# PFC_15V_PwrSRegulator.net
KiCad netlist of a schematic drawn in Altium Designer
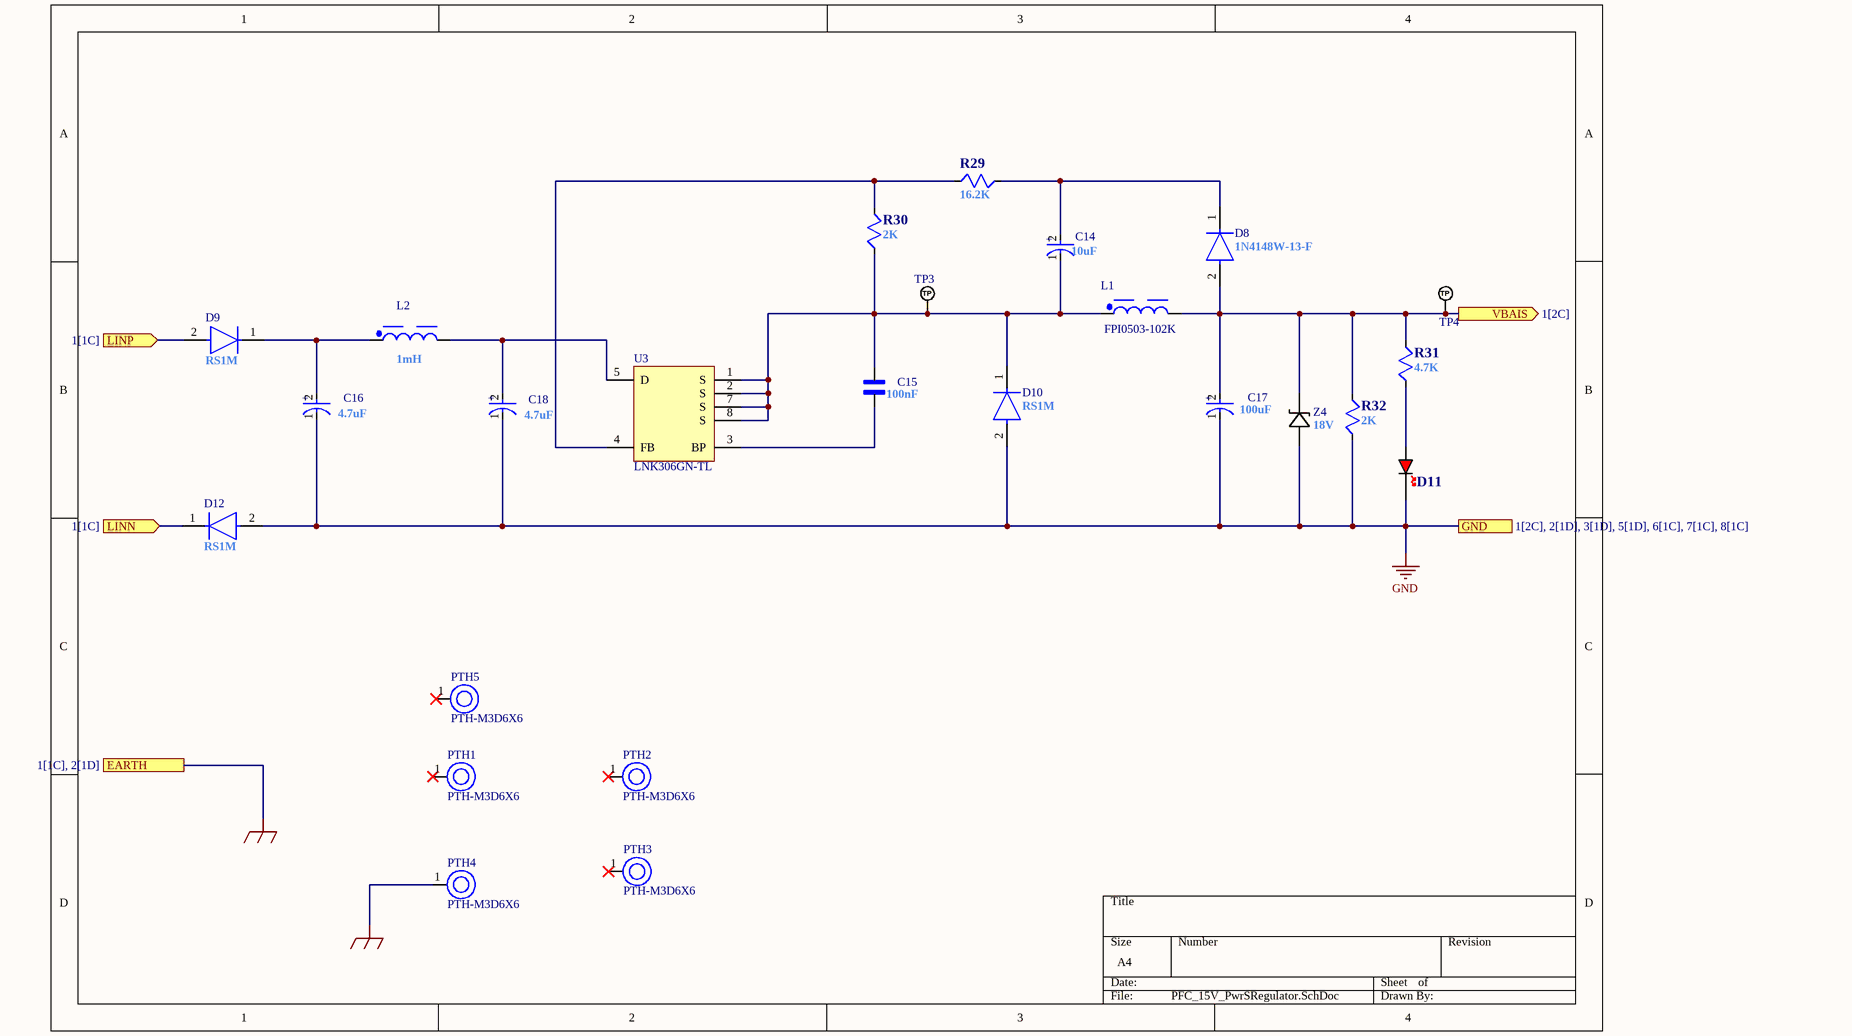
[diagram p0: PFC_15V_PwrSRegulator.SchDoc]

(export (version "E")
  (design (tool "Eeschema 10.0.6"))
  (components
    (comp (ref "C14")
      (value "SC1V106M05005VR")
      (footprint "FP-FKC-MFG")
      (description "CAP.EL.10uF 35V 5x5.3 85C SMD SAMWHA")
      (fields
        (field (name "TOLERANCE") "20%")
        (field (name "VOLTAGE") "35V")
        (field (name "CAPACITANCE") "10uF")
      )
      (libsource (lib "Altium Content Vault") (part "a00bbbee19879c290e62620ae7e47b1"))
    )
    (comp (ref "C15")
      (value "100nF")
      (footprint "CAPC3216X140N")
      (description "0.1 ÂµF Â±10% 250V Ceramic Capacitor X7R 1206 (3216 Metric)")
      (fields (field (name "MF") "KEMET") (field (name "MP") "C1206C104KARECAUTO"))
      (libsource (lib "Görev Yükü's Libary") (part "C1206C104KARECAUTO"))
    )
    (comp (ref "C16")
      (value "PKLH-400V4R7MG125-T/A5.0")
      (footprint "FP-RAD-TH-D_10_0_5-L_12_5-MFG")
      (description "CAP.EL.4u7 400V 10X12.5 5MM %20 105C LOW IMP")
      (fields (field (name "TOLERANCE") "20%") (field (name "CAPACITANCE") "4.7uF"))
      (libsource (lib "Altium Content Vault") (part "203bc49f2ac43e59fd269a8c329ed05"))
    )
    (comp (ref "C17")
      (value "CKL025M101F10PKKKV00A")
      (footprint "FP-SEV8X10_5-MFG")
      (description "CAP.EL.100uF 25V 8x10 105C 5000H AEC-Q200 SMT")
      (fields (field (name "CAPACITANCE") "100uF") (field (name "TOLERANCE") "20%"))
      (libsource (lib "Altium Content Vault") (part "203bc49f2ac43e59fd269a8c329ed05"))
    )
    (comp (ref "C18")
      (value "PKLH-400V4R7MG125-T/A5.0")
      (footprint "FP-RAD-TH-D_10_0_5-L_12_5-MFG")
      (description "CAP.EL.4u7 400V 10X12.5 5MM %20 105C LOW IMP")
      (fields (field (name "TOLERANCE") "20%") (field (name "CAPACITANCE") "4.7uF"))
      (libsource (lib "Altium Content Vault") (part "203bc49f2ac43e59fd269a8c329ed05"))
    )
    (comp (ref "D8")
      (value "1N4148W-13-F")
      (footprint "FP-SOD123-MFG")
      (description "DIODE GEN PURP 100V 150MA SOD123")
      (fields
        (field (name "OCTOPART") "https://octopart.com/1n4148w-13-f-diodes+inc.-2359612")
        (field (name "MANUFACTURER") "Diodes Inc.")
      )
      (libsource (lib "Altium Content Vault") (part "d7152d700b627762746794eb795d46e"))
    )
    (comp (ref "D9")
      (value "RS1M")
      (footprint "FP-403AE-MFG")
      (description "DIODE GEN PURP 1KV 1A SMA")
      (fields
        (field (name "OCTOPART") "https://octopart.com/rs1m-on+semiconductor-84331238")
        (field (name "MANUFACTURER") "ON Semiconductor")
      )
      (libsource (lib "Altium Content Vault") (part "d7152d700b627762746794eb795d46e"))
    )
    (comp (ref "D10")
      (value "RS1M")
      (footprint "FP-403AE-MFG")
      (description "DIODE GEN PURP 1KV 1A SMA")
      (fields
        (field (name "OCTOPART") "https://octopart.com/rs1m-on+semiconductor-84331238")
        (field (name "MANUFACTURER") "ON Semiconductor")
      )
      (libsource (lib "Altium Content Vault") (part "d7152d700b627762746794eb795d46e"))
    )
    (comp (ref "D11")
      (value "19-21/R6C-AP1Q2/4T")
      (footprint "LED_0603_RED")
      (description "LED SMD 0603 RED 28.5-72mcd 100° WATER CLEAR")
      (libsource (lib "Phil-lab") (part "LED_0603_RED"))
    )
    (comp (ref "D12")
      (value "RS1M")
      (footprint "FP-403AE-MFG")
      (description "DIODE GEN PURP 1KV 1A SMA")
      (fields
        (field (name "OCTOPART") "https://octopart.com/rs1m-on+semiconductor-84331238")
        (field (name "MANUFACTURER") "ON Semiconductor")
      )
      (libsource (lib "Altium Content Vault") (part "d7152d700b627762746794eb795d46e"))
    )
    (comp (ref "L1")
      (value "FPI0503-102K")
      (footprint "WE-LQS_6045")
      (description "POWER INDUCTOR General Purpose Inductor, 1000uH, 10%, 1 Element, SMD, 2424")
      (fields (field (name "TOLERANCE") "20%"))
      (libsource (lib "Altium Content Vault") (part "Inductor - 2"))
    )
    (comp (ref "L2")
      (value "FPI0705-102K(W0.15)")
      (footprint "WE-PD2_1054")
      (description "INDUCTOR POWER 1mH 7.8X7.0X5.0MM SMD")
      (fields (field (name "TOLERANCE") "10%") (field (name "INDUCTANCE") "1mH"))
      (libsource (lib "Altium Content Vault") (part "Inductor - 2"))
    )
    (comp (ref "PTH1")
      (value "PTH-M3D6X6")
      (footprint "PH3.2")
      (libsource (lib "Components") (part "PTH_S1"))
    )
    (comp (ref "PTH2")
      (value "PTH-M3D6X6")
      (footprint "PH3.2")
      (libsource (lib "Components") (part "PTH_S1"))
    )
    (comp (ref "PTH3")
      (value "PTH-M3D6X6")
      (footprint "PH3.2")
      (libsource (lib "Components") (part "PTH_S1"))
    )
    (comp (ref "PTH4")
      (value "PTH-M3D6X6")
      (footprint "PH3.2")
      (libsource (lib "Components") (part "PTH_S1"))
    )
    (comp (ref "PTH5")
      (value "PTH-M3D6X6")
      (footprint "PH3.2")
      (libsource (lib "Components") (part "PTH_S1"))
    )
    (comp (ref "R29")
      (value "16.2K")
      (footprint "PCB_EZ_BuckPowerDriver:RESC1608N")
      (description "RES.(1608) 0603 16.2K Ohms 1% 1/10W-S 100PPM")
      (fields (field (name "Comment") "0603SAF1622T5E"))
      (libsource (lib "*") (part "RES"))
    )
    (comp (ref "R30")
      (value "2K")
      (footprint "PCB_EZ_BuckPowerDriver:RESC1608N")
      (description "RES.(1608) 0603 2K Ohms 1% 1/5W")
      (fields (field (name "Comment") "HP03W5F2001T5E"))
      (libsource (lib "*") (part "RES"))
    )
    (comp (ref "R31")
      (value "4.7K")
      (footprint "PCB_EZ_BuckPowerDriver V2.0:RESC1608N")
      (description "RES.(1608) 0603 4.7K Ohms 1% 1/10W-S 100PPM")
      (fields (field (name "Comment") "0603SAF4701T5E"))
      (libsource (lib "WG_MainBoard_NV1") (part "RES"))
    )
    (comp (ref "R32")
      (value "2K")
      (footprint "RESC1608N")
      (description "RES.(1608) 0603 2K Ohms 1% 1/5W")
      (fields (field (name "Comment") "HP03W5F2001T5E"))
      (libsource (lib "*") (part "RES"))
    )
    (comp (ref "TP3")
      (value "TP_NOBOM")
      (footprint "PAD_RND_1MM")
      (description "Test Point Round 1mm (NO BOM)")
      (libsource (lib "Phil-lab") (part "TEST_POINT_RND_1MM"))
    )
    (comp (ref "TP4")
      (value "TP_NOBOM")
      (footprint "PAD_RND_1MM")
      (description "Test Point Round 1mm (NO BOM)")
      (libsource (lib "Phil-lab") (part "TEST_POINT_RND_1MM"))
    )
    (comp (ref "U3")
      (value "LNK306GN-TL")
      (footprint "PI-SMD-8B-7_V")
      (fields (field (name "MANUFACTURER") "Power Integrations"))
      (libsource (lib "Altium Content Vault") (part "PI-LNK30X-G_P-7"))
    )
    (comp (ref "Z4")
      (value "MMSZ5248BS-7-F")
      (footprint "ZDO_SOD323_DIO-M")
      (description "Zener Diode 18 V 200 mW ±5% Surface Mount SOD-323")
      (fields
        (field (name "TYPE") "18V")
        (field (name "COPYRIGHT") "Copyright (C) 2026 Ultra Librarian. All rights reserved.")
      )
      (libsource (lib "Görev Yükü's Libary") (part "MMSZ5248BS-7-F"))
    )
  )
  (nets
    (net (code "1") (name "/LINN") (class "Default")
      (node (ref "D12") (pin "1") (pinfunction "C_1") (pintype "passive"))
    )
    (net (code "2") (name "/LINP") (class "Default")
      (node (ref "D9") (pin "2") (pinfunction "A_2") (pintype "passive"))
    )
    (net (code "3") (name "/VBAIS") (class "Default")
      (node (ref "C17") (pin "2") (pinfunction "A_2") (pintype "passive"))
      (node (ref "D8") (pin "2") (pinfunction "A_2") (pintype "passive"))
      (node (ref "L1") (pin "2") (pinfunction "2_2") (pintype "passive"))
      (node (ref "R31") (pin "1") (pinfunction "1_1") (pintype "passive"))
      (node (ref "R32") (pin "1") (pinfunction "1_1") (pintype "passive"))
      (node (ref "TP4") (pin "1") (pinfunction "TP_1") (pintype "passive"))
      (node (ref "Z4") (pin "1") (pinfunction "1_1") (pintype "passive"))
    )
    (net (code "4") (name "EARTH") (class "Default")
      (node (ref "PTH4") (pin "1") (pinfunction "1_1") (pintype "passive"))
    )
    (net (code "5") (name "GND") (class "Default")
      (node (ref "C16") (pin "1") (pinfunction "C_1") (pintype "passive"))
      (node (ref "C17") (pin "1") (pinfunction "C_1") (pintype "passive"))
      (node (ref "C18") (pin "1") (pinfunction "C_1") (pintype "passive"))
      (node (ref "D10") (pin "2") (pinfunction "A_2") (pintype "passive"))
      (node (ref "D11") (pin "K") (pinfunction "K_K") (pintype "passive"))
      (node (ref "D12") (pin "2") (pinfunction "A_2") (pintype "passive"))
      (node (ref "R32") (pin "2") (pinfunction "2_2") (pintype "passive"))
      (node (ref "Z4") (pin "2") (pinfunction "2_2") (pintype "passive"))
    )
    (net (code "6") (name "Net-(C14-A)") (class "Default")
      (node (ref "C14") (pin "2") (pinfunction "A_2") (pintype "passive"))
      (node (ref "D8") (pin "1") (pinfunction "C_1") (pintype "passive"))
      (node (ref "R29") (pin "1") (pinfunction "1_1") (pintype "passive"))
    )
    (net (code "7") (name "Net-(C14-C)") (class "Default")
      (node (ref "C14") (pin "1") (pinfunction "C_1") (pintype "passive"))
      (node (ref "C15") (pin "2") (pinfunction "2_2") (pintype "passive"))
      (node (ref "D10") (pin "1") (pinfunction "C_1") (pintype "passive"))
      (node (ref "L1") (pin "1") (pinfunction "1_1") (pintype "passive"))
      (node (ref "R30") (pin "2") (pinfunction "2_2") (pintype "passive"))
      (node (ref "TP3") (pin "1") (pinfunction "TP_1") (pintype "passive"))
      (node (ref "U3") (pin "1") (pinfunction "S_1") (pintype "passive"))
      (node (ref "U3") (pin "2") (pinfunction "S_2") (pintype "passive"))
      (node (ref "U3") (pin "7") (pinfunction "S_7") (pintype "passive"))
      (node (ref "U3") (pin "8") (pinfunction "S_8") (pintype "passive"))
    )
    (net (code "8") (name "Net-(C16-A)") (class "Default")
      (node (ref "C16") (pin "2") (pinfunction "A_2") (pintype "passive"))
      (node (ref "D9") (pin "1") (pinfunction "C_1") (pintype "passive"))
      (node (ref "L2") (pin "1") (pinfunction "1_1") (pintype "passive"))
    )
    (net (code "9") (name "Net-(C18-A)") (class "Default")
      (node (ref "C18") (pin "2") (pinfunction "A_2") (pintype "passive"))
      (node (ref "L2") (pin "2") (pinfunction "2_2") (pintype "passive"))
      (node (ref "U3") (pin "5") (pinfunction "D_5") (pintype "passive"))
    )
    (net (code "10") (name "Net-(D11-PadA)") (class "Default")
      (node (ref "D11") (pin "A") (pinfunction "A_A") (pintype "passive"))
      (node (ref "R31") (pin "2") (pinfunction "2_2") (pintype "passive"))
    )
    (net (code "11") (name "Net-(U3-BP)") (class "Default")
      (node (ref "C15") (pin "1") (pinfunction "1_1") (pintype "passive"))
      (node (ref "U3") (pin "3") (pinfunction "BP_3") (pintype "passive"))
    )
    (net (code "12") (name "Net-(U3-FB)") (class "Default")
      (node (ref "R29") (pin "2") (pinfunction "2_2") (pintype "passive"))
      (node (ref "R30") (pin "1") (pinfunction "1_1") (pintype "passive"))
      (node (ref "U3") (pin "4") (pinfunction "FB_4") (pintype "passive"))
    )
    (net (code "13") (name "unconnected-(PTH1-Pad1)") (class "Default")
      (node (ref "PTH1") (pin "1") (pinfunction "1_1") (pintype "passive+no_connect"))
    )
    (net (code "14") (name "unconnected-(PTH2-Pad1)") (class "Default")
      (node (ref "PTH2") (pin "1") (pinfunction "1_1") (pintype "passive+no_connect"))
    )
    (net (code "15") (name "unconnected-(PTH3-Pad1)") (class "Default")
      (node (ref "PTH3") (pin "1") (pinfunction "1_1") (pintype "passive+no_connect"))
    )
    (net (code "16") (name "unconnected-(PTH5-Pad1)") (class "Default")
      (node (ref "PTH5") (pin "1") (pinfunction "1_1") (pintype "passive+no_connect"))
    )
  )
)
